# audio.net
KiCad netlist of a schematic drawn in EAGLE
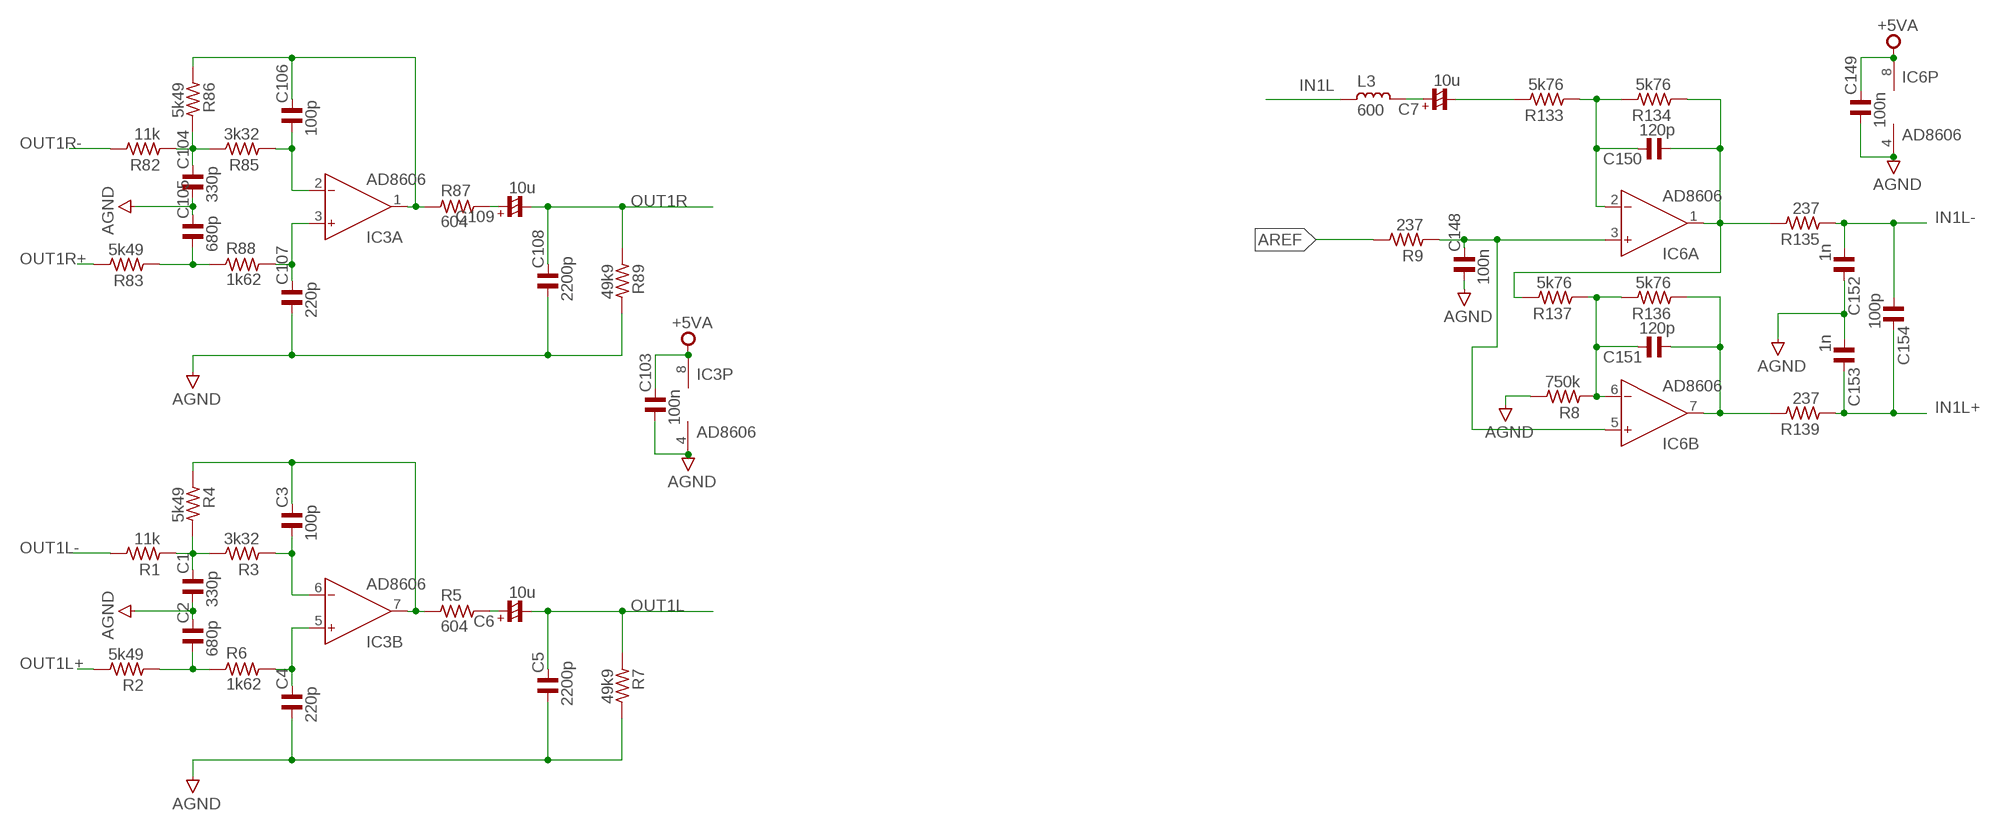
[diagram p0: schematic, sheet 1]

(export (version "E")
  (design (tool "Eeschema 10.0.6"))
  (components
    (comp (ref "C1")
      (value "330p")
      (footprint "eagle-import:C0603")
      (libsource (lib "eagle-import") (part "C_0603"))
    )
    (comp (ref "C2")
      (value "680p")
      (footprint "eagle-import:C0603")
      (libsource (lib "eagle-import") (part "C_0603"))
    )
    (comp (ref "C3")
      (value "100p")
      (footprint "eagle-import:C0603")
      (libsource (lib "eagle-import") (part "C_0603"))
    )
    (comp (ref "C4")
      (value "220p")
      (footprint "eagle-import:C0603")
      (libsource (lib "eagle-import") (part "C_0603"))
    )
    (comp (ref "C5")
      (value "2200p")
      (footprint "eagle-import:C0603")
      (libsource (lib "eagle-import") (part "C_0603"))
    )
    (comp (ref "C6")
      (value "10u")
      (footprint "eagle-import:C1206_T")
      (libsource (lib "eagle-import") (part "CP_1206/T"))
    )
    (comp (ref "C7")
      (value "10u")
      (footprint "eagle-import:C1206_T")
      (libsource (lib "eagle-import") (part "CP_1206/T"))
    )
    (comp (ref "C103")
      (value "100n")
      (footprint "eagle-import:C0603")
      (libsource (lib "eagle-import") (part "C_0603"))
    )
    (comp (ref "C104")
      (value "330p")
      (footprint "eagle-import:C0603")
      (libsource (lib "eagle-import") (part "C_0603"))
    )
    (comp (ref "C105")
      (value "680p")
      (footprint "eagle-import:C0603")
      (libsource (lib "eagle-import") (part "C_0603"))
    )
    (comp (ref "C106")
      (value "100p")
      (footprint "eagle-import:C0603")
      (libsource (lib "eagle-import") (part "C_0603"))
    )
    (comp (ref "C107")
      (value "220p")
      (footprint "eagle-import:C0603")
      (libsource (lib "eagle-import") (part "C_0603"))
    )
    (comp (ref "C108")
      (value "2200p")
      (footprint "eagle-import:C0603")
      (libsource (lib "eagle-import") (part "C_0603"))
    )
    (comp (ref "C109")
      (value "10u")
      (footprint "eagle-import:C1206_T")
      (libsource (lib "eagle-import") (part "CP_1206/T"))
    )
    (comp (ref "C148")
      (value "100n")
      (footprint "eagle-import:C0603")
      (libsource (lib "eagle-import") (part "C_0603"))
    )
    (comp (ref "C149")
      (value "100n")
      (footprint "eagle-import:C0603")
      (libsource (lib "eagle-import") (part "C_0603"))
    )
    (comp (ref "C150")
      (value "120p")
      (footprint "eagle-import:C0603")
      (libsource (lib "eagle-import") (part "C_0603"))
    )
    (comp (ref "C151")
      (value "120p")
      (footprint "eagle-import:C0603")
      (libsource (lib "eagle-import") (part "C_0603"))
    )
    (comp (ref "C152")
      (value "1n")
      (footprint "eagle-import:C0603")
      (libsource (lib "eagle-import") (part "C_0603"))
    )
    (comp (ref "C153")
      (value "1n")
      (footprint "eagle-import:C0603")
      (libsource (lib "eagle-import") (part "C_0603"))
    )
    (comp (ref "C154")
      (value "100p")
      (footprint "eagle-import:C0603")
      (libsource (lib "eagle-import") (part "C_0603"))
    )
    (comp (ref "IC3")
      (value "AD8606")
      (footprint "eagle-import:SO8")
      (fields (field (name "MPN") "AD8607ARMZ-R2"))
      (libsource (lib "eagle-import") (part "AD8607R"))
    )
    (comp (ref "IC6")
      (value "AD8606")
      (footprint "eagle-import:SO8")
      (fields (field (name "MPN") "AD8607ARMZ-R2"))
      (libsource (lib "eagle-import") (part "AD8607R"))
    )
    (comp (ref "L3")
      (value "600")
      (footprint "eagle-import:L1206")
      (libsource (lib "eagle-import") (part "L_1206"))
    )
    (comp (ref "R1")
      (value "11k")
      (footprint "eagle-import:R0603")
      (libsource (lib "eagle-import") (part "R_0603"))
    )
    (comp (ref "R2")
      (value "5k49")
      (footprint "eagle-import:R0603")
      (libsource (lib "eagle-import") (part "R_0603"))
    )
    (comp (ref "R3")
      (value "3k32")
      (footprint "eagle-import:R0603")
      (libsource (lib "eagle-import") (part "R_0603"))
    )
    (comp (ref "R4")
      (value "5k49")
      (footprint "eagle-import:R0603")
      (libsource (lib "eagle-import") (part "R_0603"))
    )
    (comp (ref "R5")
      (value "604")
      (footprint "eagle-import:R0603")
      (libsource (lib "eagle-import") (part "R_0603"))
    )
    (comp (ref "R6")
      (value "1k62")
      (footprint "eagle-import:R0603")
      (libsource (lib "eagle-import") (part "R_0603"))
    )
    (comp (ref "R7")
      (value "49k9")
      (footprint "eagle-import:R0603")
      (libsource (lib "eagle-import") (part "R_0603"))
    )
    (comp (ref "R8")
      (value "750k")
      (footprint "eagle-import:R0603")
      (libsource (lib "eagle-import") (part "R_0603"))
    )
    (comp (ref "R9")
      (value "237")
      (footprint "eagle-import:R0603")
      (libsource (lib "eagle-import") (part "R_0603"))
    )
    (comp (ref "R82")
      (value "11k")
      (footprint "eagle-import:R0603")
      (libsource (lib "eagle-import") (part "R_0603"))
    )
    (comp (ref "R83")
      (value "5k49")
      (footprint "eagle-import:R0603")
      (libsource (lib "eagle-import") (part "R_0603"))
    )
    (comp (ref "R85")
      (value "3k32")
      (footprint "eagle-import:R0603")
      (libsource (lib "eagle-import") (part "R_0603"))
    )
    (comp (ref "R86")
      (value "5k49")
      (footprint "eagle-import:R0603")
      (libsource (lib "eagle-import") (part "R_0603"))
    )
    (comp (ref "R87")
      (value "604")
      (footprint "eagle-import:R0603")
      (libsource (lib "eagle-import") (part "R_0603"))
    )
    (comp (ref "R88")
      (value "1k62")
      (footprint "eagle-import:R0603")
      (libsource (lib "eagle-import") (part "R_0603"))
    )
    (comp (ref "R89")
      (value "49k9")
      (footprint "eagle-import:R0603")
      (libsource (lib "eagle-import") (part "R_0603"))
    )
    (comp (ref "R133")
      (value "5k76")
      (footprint "eagle-import:R0603")
      (libsource (lib "eagle-import") (part "R_0603"))
    )
    (comp (ref "R134")
      (value "5k76")
      (footprint "eagle-import:R0603")
      (libsource (lib "eagle-import") (part "R_0603"))
    )
    (comp (ref "R135")
      (value "237")
      (footprint "eagle-import:R0603")
      (libsource (lib "eagle-import") (part "R_0603"))
    )
    (comp (ref "R136")
      (value "5k76")
      (footprint "eagle-import:R0603")
      (libsource (lib "eagle-import") (part "R_0603"))
    )
    (comp (ref "R137")
      (value "5k76")
      (footprint "eagle-import:R0603")
      (libsource (lib "eagle-import") (part "R_0603"))
    )
    (comp (ref "R139")
      (value "237")
      (footprint "eagle-import:R0603")
      (libsource (lib "eagle-import") (part "R_0603"))
    )
  )
  (nets
    (net (code "1") (name "+5VA") (class "Default")
      (node (ref "C103") (pin "2") (pinfunction "2_2") (pintype "passive"))
      (node (ref "C149") (pin "2") (pinfunction "2_2") (pintype "passive"))
      (node (ref "IC3") (pin "8") (pinfunction "V+_8") (pintype "power_in"))
      (node (ref "IC6") (pin "8") (pinfunction "V+_8") (pintype "power_in"))
    )
    (net (code "2") (name "/IN1L") (class "Default")
      (node (ref "L3") (pin "2") (pinfunction "2_2") (pintype "passive"))
    )
    (net (code "3") (name "/IN1L+") (class "Default")
      (node (ref "C153") (pin "2") (pinfunction "2_2") (pintype "passive"))
      (node (ref "C154") (pin "2") (pinfunction "2_2") (pintype "passive"))
      (node (ref "R139") (pin "1") (pinfunction "1_1") (pintype "passive"))
    )
    (net (code "4") (name "/IN1L-") (class "Default")
      (node (ref "C152") (pin "1") (pinfunction "1_1") (pintype "passive"))
      (node (ref "C154") (pin "1") (pinfunction "1_1") (pintype "passive"))
      (node (ref "R135") (pin "1") (pinfunction "1_1") (pintype "passive"))
    )
    (net (code "5") (name "/OUT1L") (class "Default")
      (node (ref "C5") (pin "2") (pinfunction "2_2") (pintype "passive"))
      (node (ref "C6") (pin "-") (pinfunction "-_-") (pintype "passive"))
      (node (ref "R7") (pin "1") (pinfunction "1_1") (pintype "passive"))
    )
    (net (code "6") (name "/OUT1L+") (class "Default")
      (node (ref "R2") (pin "2") (pinfunction "2_2") (pintype "passive"))
    )
    (net (code "7") (name "/OUT1L-") (class "Default")
      (node (ref "R1") (pin "2") (pinfunction "2_2") (pintype "passive"))
    )
    (net (code "8") (name "/OUT1R") (class "Default")
      (node (ref "C108") (pin "2") (pinfunction "2_2") (pintype "passive"))
      (node (ref "C109") (pin "-") (pinfunction "-_-") (pintype "passive"))
      (node (ref "R89") (pin "1") (pinfunction "1_1") (pintype "passive"))
    )
    (net (code "9") (name "/OUT1R+") (class "Default")
      (node (ref "R83") (pin "2") (pinfunction "2_2") (pintype "passive"))
    )
    (net (code "10") (name "/OUT1R-") (class "Default")
      (node (ref "R82") (pin "2") (pinfunction "2_2") (pintype "passive"))
    )
    (net (code "11") (name "AGND") (class "Default")
      (node (ref "C1") (pin "1") (pinfunction "1_1") (pintype "passive"))
      (node (ref "C103") (pin "1") (pinfunction "1_1") (pintype "passive"))
      (node (ref "C104") (pin "1") (pinfunction "1_1") (pintype "passive"))
      (node (ref "C105") (pin "2") (pinfunction "2_2") (pintype "passive"))
      (node (ref "C107") (pin "1") (pinfunction "1_1") (pintype "passive"))
      (node (ref "C108") (pin "1") (pinfunction "1_1") (pintype "passive"))
      (node (ref "C148") (pin "1") (pinfunction "1_1") (pintype "passive"))
      (node (ref "C149") (pin "1") (pinfunction "1_1") (pintype "passive"))
      (node (ref "C152") (pin "2") (pinfunction "2_2") (pintype "passive"))
      (node (ref "C153") (pin "1") (pinfunction "1_1") (pintype "passive"))
      (node (ref "C2") (pin "2") (pinfunction "2_2") (pintype "passive"))
      (node (ref "C4") (pin "1") (pinfunction "1_1") (pintype "passive"))
      (node (ref "C5") (pin "1") (pinfunction "1_1") (pintype "passive"))
      (node (ref "IC3") (pin "4") (pinfunction "V-_4") (pintype "power_in"))
      (node (ref "IC6") (pin "4") (pinfunction "V-_4") (pintype "power_in"))
      (node (ref "R7") (pin "2") (pinfunction "2_2") (pintype "passive"))
      (node (ref "R8") (pin "2") (pinfunction "2_2") (pintype "passive"))
      (node (ref "R89") (pin "2") (pinfunction "2_2") (pintype "passive"))
    )
    (net (code "12") (name "AREF") (class "Default")
      (node (ref "R9") (pin "2") (pinfunction "2_2") (pintype "passive"))
    )
    (net (code "13") (name "Net-(C1-Pad2)") (class "Default")
      (node (ref "C1") (pin "2") (pinfunction "2_2") (pintype "passive"))
      (node (ref "R1") (pin "1") (pinfunction "1_1") (pintype "passive"))
      (node (ref "R3") (pin "2") (pinfunction "2_2") (pintype "passive"))
      (node (ref "R4") (pin "2") (pinfunction "2_2") (pintype "passive"))
    )
    (net (code "14") (name "Net-(C2-Pad1)") (class "Default")
      (node (ref "C2") (pin "1") (pinfunction "1_1") (pintype "passive"))
      (node (ref "R2") (pin "1") (pinfunction "1_1") (pintype "passive"))
      (node (ref "R6") (pin "1") (pinfunction "1_1") (pintype "passive"))
    )
    (net (code "15") (name "Net-(C6-Pad+)") (class "Default")
      (node (ref "C6") (pin "+") (pinfunction "+_+") (pintype "passive"))
      (node (ref "R5") (pin "2") (pinfunction "2_2") (pintype "passive"))
    )
    (net (code "16") (name "Net-(C7-Pad+)") (class "Default")
      (node (ref "C7") (pin "+") (pinfunction "+_+") (pintype "passive"))
      (node (ref "L3") (pin "1") (pinfunction "1_1") (pintype "passive"))
    )
    (net (code "17") (name "Net-(C7-Pad-)") (class "Default")
      (node (ref "C7") (pin "-") (pinfunction "-_-") (pintype "passive"))
      (node (ref "R133") (pin "2") (pinfunction "2_2") (pintype "passive"))
    )
    (net (code "18") (name "Net-(C104-Pad2)") (class "Default")
      (node (ref "C104") (pin "2") (pinfunction "2_2") (pintype "passive"))
      (node (ref "R82") (pin "1") (pinfunction "1_1") (pintype "passive"))
      (node (ref "R85") (pin "2") (pinfunction "2_2") (pintype "passive"))
      (node (ref "R86") (pin "2") (pinfunction "2_2") (pintype "passive"))
    )
    (net (code "19") (name "Net-(C105-Pad1)") (class "Default")
      (node (ref "C105") (pin "1") (pinfunction "1_1") (pintype "passive"))
      (node (ref "R83") (pin "1") (pinfunction "1_1") (pintype "passive"))
      (node (ref "R88") (pin "1") (pinfunction "1_1") (pintype "passive"))
    )
    (net (code "20") (name "Net-(C109-Pad+)") (class "Default")
      (node (ref "C109") (pin "+") (pinfunction "+_+") (pintype "passive"))
      (node (ref "R87") (pin "2") (pinfunction "2_2") (pintype "passive"))
    )
    (net (code "21") (name "Net-(IC3A-IN+)") (class "Default")
      (node (ref "C107") (pin "2") (pinfunction "2_2") (pintype "passive"))
      (node (ref "IC3") (pin "3") (pinfunction "IN+_3") (pintype "input"))
      (node (ref "R88") (pin "2") (pinfunction "2_2") (pintype "passive"))
    )
    (net (code "22") (name "Net-(IC3A-IN-)") (class "Default")
      (node (ref "C106") (pin "1") (pinfunction "1_1") (pintype "passive"))
      (node (ref "IC3") (pin "2") (pinfunction "IN-_2") (pintype "input"))
      (node (ref "R85") (pin "1") (pinfunction "1_1") (pintype "passive"))
    )
    (net (code "23") (name "Net-(IC3A-OUT)") (class "Default")
      (node (ref "C106") (pin "2") (pinfunction "2_2") (pintype "passive"))
      (node (ref "IC3") (pin "1") (pinfunction "OUT_1") (pintype "output"))
      (node (ref "R86") (pin "1") (pinfunction "1_1") (pintype "passive"))
      (node (ref "R87") (pin "1") (pinfunction "1_1") (pintype "passive"))
    )
    (net (code "24") (name "Net-(IC3B-IN+)") (class "Default")
      (node (ref "C4") (pin "2") (pinfunction "2_2") (pintype "passive"))
      (node (ref "IC3") (pin "5") (pinfunction "IN+_5") (pintype "input"))
      (node (ref "R6") (pin "2") (pinfunction "2_2") (pintype "passive"))
    )
    (net (code "25") (name "Net-(IC3B-IN-)") (class "Default")
      (node (ref "C3") (pin "1") (pinfunction "1_1") (pintype "passive"))
      (node (ref "IC3") (pin "6") (pinfunction "IN-_6") (pintype "input"))
      (node (ref "R3") (pin "1") (pinfunction "1_1") (pintype "passive"))
    )
    (net (code "26") (name "Net-(IC3B-OUT)") (class "Default")
      (node (ref "C3") (pin "2") (pinfunction "2_2") (pintype "passive"))
      (node (ref "IC3") (pin "7") (pinfunction "OUT_7") (pintype "output"))
      (node (ref "R4") (pin "1") (pinfunction "1_1") (pintype "passive"))
      (node (ref "R5") (pin "1") (pinfunction "1_1") (pintype "passive"))
    )
    (net (code "27") (name "Net-(IC6A-IN+)") (class "Default")
      (node (ref "C148") (pin "2") (pinfunction "2_2") (pintype "passive"))
      (node (ref "IC6") (pin "3") (pinfunction "IN+_3") (pintype "input"))
      (node (ref "IC6") (pin "5") (pinfunction "IN+_5") (pintype "input"))
      (node (ref "R9") (pin "1") (pinfunction "1_1") (pintype "passive"))
    )
    (net (code "28") (name "Net-(IC6A-IN-)") (class "Default")
      (node (ref "C150") (pin "2") (pinfunction "2_2") (pintype "passive"))
      (node (ref "IC6") (pin "2") (pinfunction "IN-_2") (pintype "input"))
      (node (ref "R133") (pin "1") (pinfunction "1_1") (pintype "passive"))
      (node (ref "R134") (pin "2") (pinfunction "2_2") (pintype "passive"))
    )
    (net (code "29") (name "Net-(IC6A-OUT)") (class "Default")
      (node (ref "C150") (pin "1") (pinfunction "1_1") (pintype "passive"))
      (node (ref "IC6") (pin "1") (pinfunction "OUT_1") (pintype "output"))
      (node (ref "R134") (pin "1") (pinfunction "1_1") (pintype "passive"))
      (node (ref "R135") (pin "2") (pinfunction "2_2") (pintype "passive"))
      (node (ref "R137") (pin "2") (pinfunction "2_2") (pintype "passive"))
    )
    (net (code "30") (name "Net-(IC6B-IN-)") (class "Default")
      (node (ref "C151") (pin "2") (pinfunction "2_2") (pintype "passive"))
      (node (ref "IC6") (pin "6") (pinfunction "IN-_6") (pintype "input"))
      (node (ref "R136") (pin "2") (pinfunction "2_2") (pintype "passive"))
      (node (ref "R137") (pin "1") (pinfunction "1_1") (pintype "passive"))
      (node (ref "R8") (pin "1") (pinfunction "1_1") (pintype "passive"))
    )
    (net (code "31") (name "Net-(IC6B-OUT)") (class "Default")
      (node (ref "C151") (pin "1") (pinfunction "1_1") (pintype "passive"))
      (node (ref "IC6") (pin "7") (pinfunction "OUT_7") (pintype "output"))
      (node (ref "R136") (pin "1") (pinfunction "1_1") (pintype "passive"))
      (node (ref "R139") (pin "2") (pinfunction "2_2") (pintype "passive"))
    )
  )
)
